# SKAARDUINO_v3_1_back.net
KiCad netlist of a schematic drawn in EAGLE
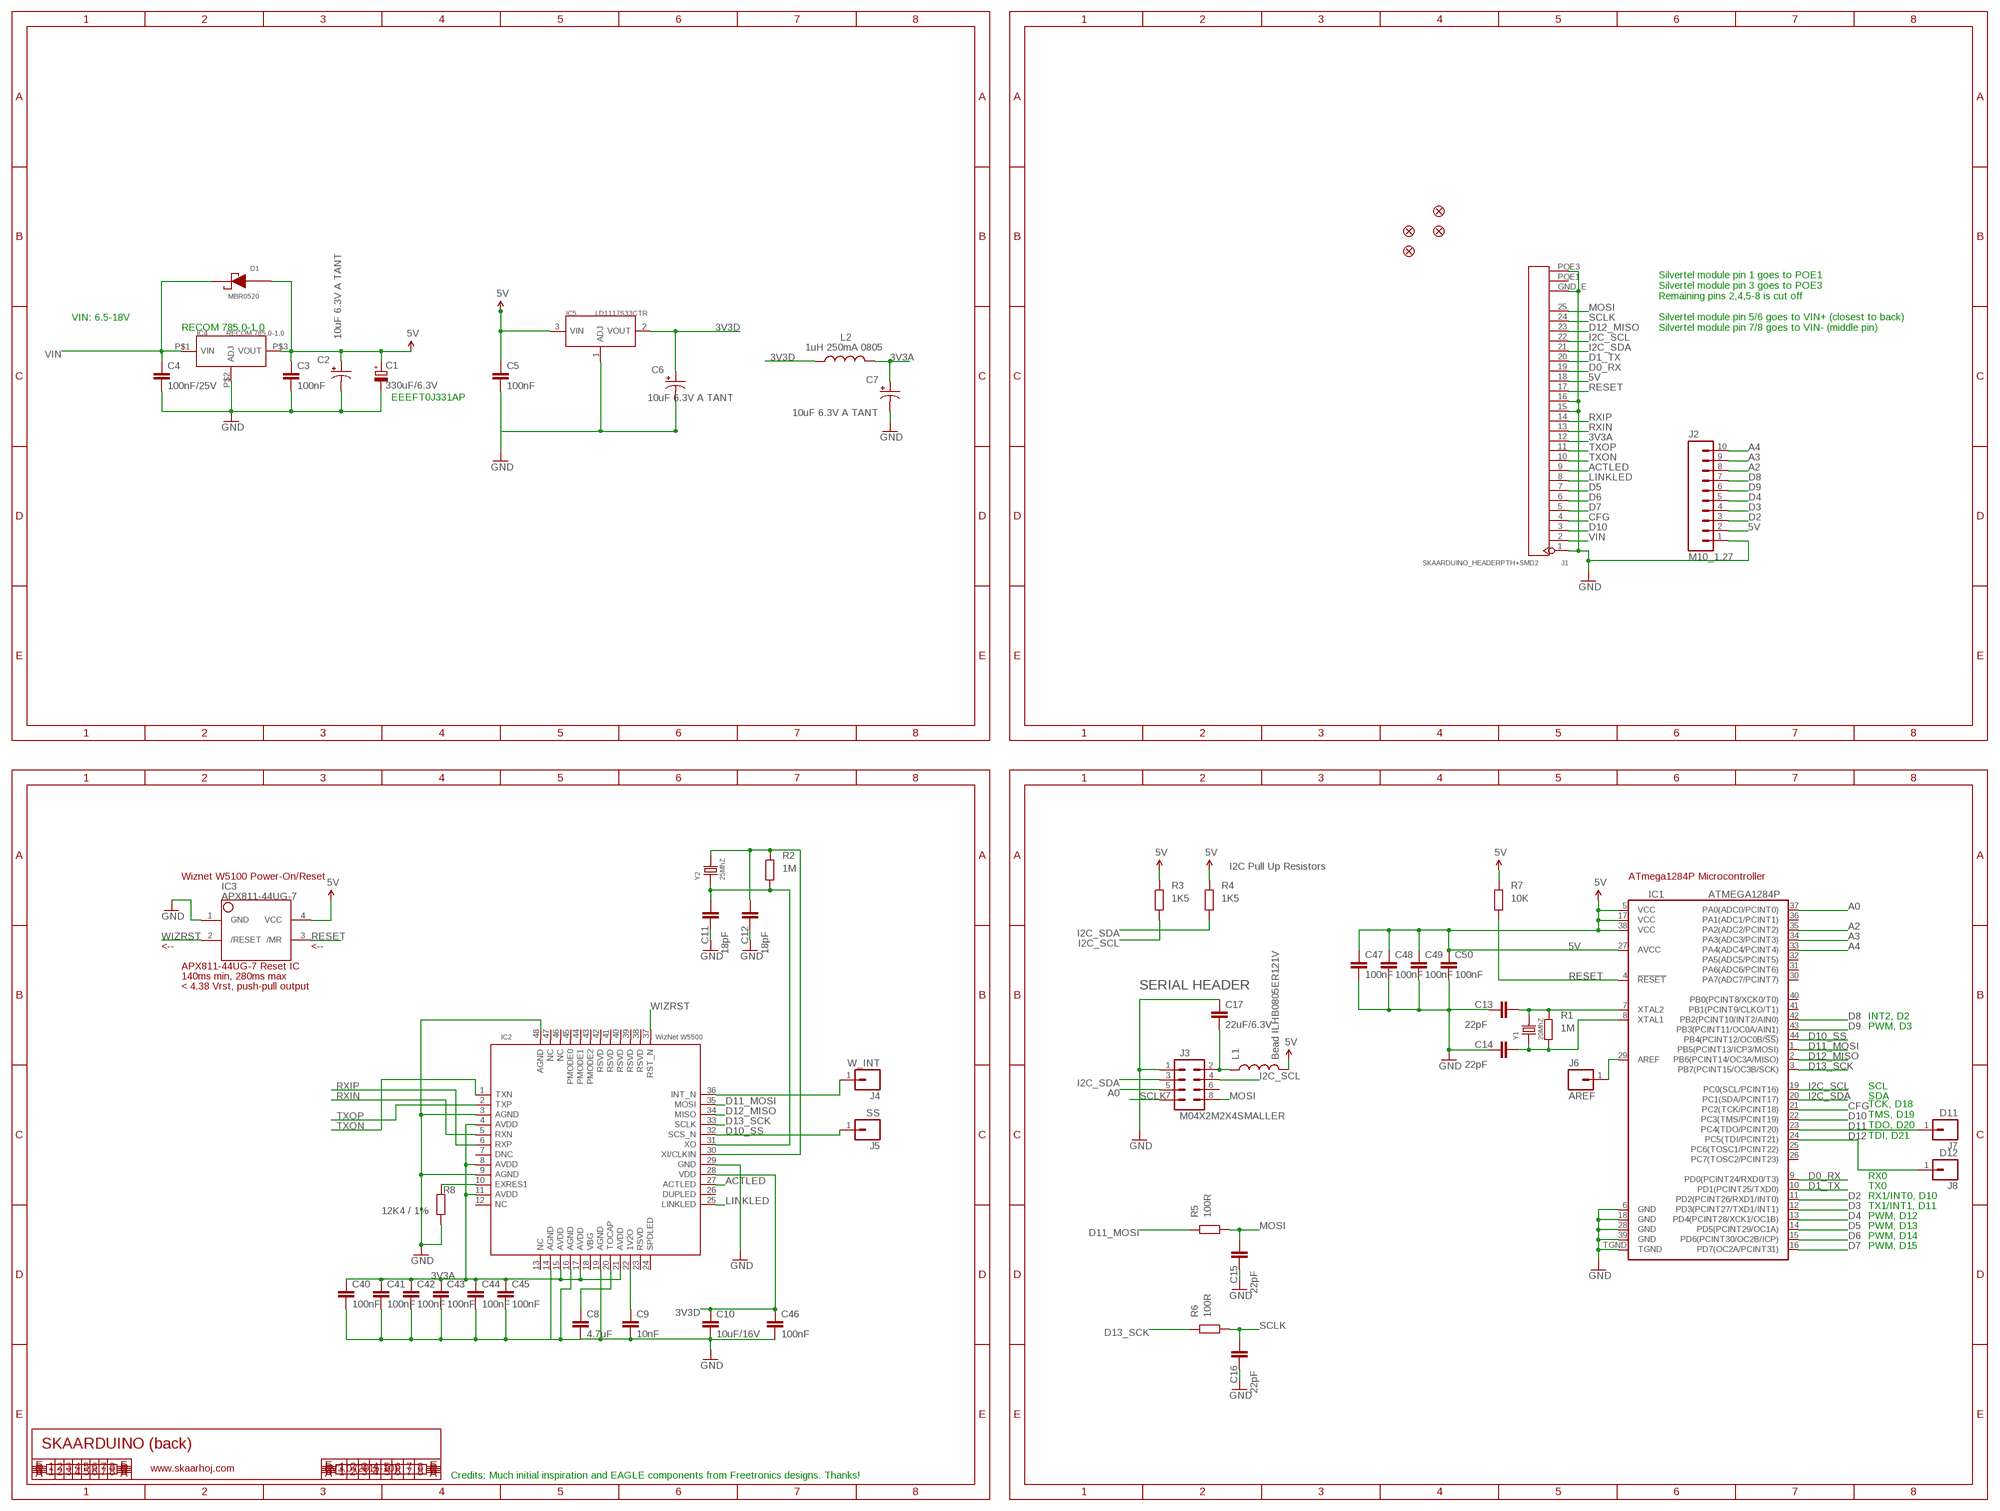
[diagram p0: schematic, sheet 1]

(export (version "E")
  (design (tool "Eeschema 10.0.6"))
  (components
    (comp (ref "C1")
      (value "330uF/6.3V")
      (footprint "eagle-import:PANASONIC_D")
      (libsource (lib "eagle-import") (part "CPOL-EUD"))
    )
    (comp (ref "C2")
      (value "10uF 6.3V A TANT")
      (footprint "eagle-import:EIA3216")
      (libsource (lib "eagle-import") (part "CAP_POL1206"))
    )
    (comp (ref "C3")
      (value "100nF")
      (footprint "eagle-import:0402C")
      (libsource (lib "eagle-import") (part "C-EU0402C"))
    )
    (comp (ref "C4")
      (value "100nF/25V")
      (footprint "eagle-import:0402C")
      (libsource (lib "eagle-import") (part "C-EU0402C"))
    )
    (comp (ref "C5")
      (value "100nF")
      (footprint "eagle-import:0402C")
      (libsource (lib "eagle-import") (part "C-EU0402C"))
    )
    (comp (ref "C6")
      (value "10uF 6.3V A TANT")
      (footprint "eagle-import:EIA3216")
      (libsource (lib "eagle-import") (part "CAP_POL1206"))
    )
    (comp (ref "C7")
      (value "10uF 6.3V A TANT")
      (footprint "eagle-import:EIA3216")
      (libsource (lib "eagle-import") (part "CAP_POL1206"))
    )
    (comp (ref "C8")
      (value "4.7uF")
      (footprint "eagle-import:0805")
      (libsource (lib "eagle-import") (part "CAP0805"))
    )
    (comp (ref "C9")
      (value "10nF")
      (footprint "eagle-import:0402C")
      (libsource (lib "eagle-import") (part "C-EU0402C"))
    )
    (comp (ref "C10")
      (value "10uF/16V")
      (footprint "eagle-import:0805")
      (libsource (lib "eagle-import") (part "CAP0805"))
    )
    (comp (ref "C11")
      (value "18pF")
      (footprint "eagle-import:0402C")
      (libsource (lib "eagle-import") (part "C-EU0402C"))
    )
    (comp (ref "C12")
      (value "18pF")
      (footprint "eagle-import:0402C")
      (libsource (lib "eagle-import") (part "C-EU0402C"))
    )
    (comp (ref "C13")
      (value "22pF")
      (footprint "eagle-import:0402C")
      (libsource (lib "eagle-import") (part "C-EU0402C"))
    )
    (comp (ref "C14")
      (value "22pF")
      (footprint "eagle-import:0402C")
      (libsource (lib "eagle-import") (part "C-EU0402C"))
    )
    (comp (ref "C15")
      (value "22pF")
      (footprint "eagle-import:0402C")
      (libsource (lib "eagle-import") (part "C-EU0402C"))
    )
    (comp (ref "C16")
      (value "22pF")
      (footprint "eagle-import:0402C")
      (libsource (lib "eagle-import") (part "C-EU0402C"))
    )
    (comp (ref "C17")
      (value "22uF/6.3V")
      (footprint "eagle-import:0805")
      (libsource (lib "eagle-import") (part "CAP0805"))
    )
    (comp (ref "C40")
      (value "100nF")
      (footprint "eagle-import:0402C")
      (libsource (lib "eagle-import") (part "C-EU0402C"))
    )
    (comp (ref "C41")
      (value "100nF")
      (footprint "eagle-import:0402C")
      (libsource (lib "eagle-import") (part "C-EU0402C"))
    )
    (comp (ref "C42")
      (value "100nF")
      (footprint "eagle-import:0402C")
      (libsource (lib "eagle-import") (part "C-EU0402C"))
    )
    (comp (ref "C43")
      (value "100nF")
      (footprint "eagle-import:0402C")
      (libsource (lib "eagle-import") (part "C-EU0402C"))
    )
    (comp (ref "C44")
      (value "100nF")
      (footprint "eagle-import:0402C")
      (libsource (lib "eagle-import") (part "C-EU0402C"))
    )
    (comp (ref "C45")
      (value "100nF")
      (footprint "eagle-import:0402C")
      (libsource (lib "eagle-import") (part "C-EU0402C"))
    )
    (comp (ref "C46")
      (value "100nF")
      (footprint "eagle-import:0402C")
      (libsource (lib "eagle-import") (part "C-EU0402C"))
    )
    (comp (ref "C47")
      (value "100nF")
      (footprint "eagle-import:0402C")
      (libsource (lib "eagle-import") (part "C-EU0402C"))
    )
    (comp (ref "C48")
      (value "100nF")
      (footprint "eagle-import:0402C")
      (libsource (lib "eagle-import") (part "C-EU0402C"))
    )
    (comp (ref "C49")
      (value "100nF")
      (footprint "eagle-import:0402C")
      (libsource (lib "eagle-import") (part "C-EU0402C"))
    )
    (comp (ref "C50")
      (value "100nF")
      (footprint "eagle-import:0402C")
      (libsource (lib "eagle-import") (part "C-EU0402C"))
    )
    (comp (ref "D1")
      (value "MBR0520")
      (footprint "eagle-import:SOD-123")
      (libsource (lib "eagle-import") (part "MBR0520"))
    )
    (comp (ref "FID1")
      (value "FIDUCIAL1X2.5")
      (footprint "eagle-import:FIDUCIAL-1X2.5")
      (libsource (lib "eagle-import") (part "FIDUCIAL1X2.5"))
    )
    (comp (ref "FID2")
      (value "FIDUCIAL1X2.5")
      (footprint "eagle-import:FIDUCIAL-1X2.5")
      (libsource (lib "eagle-import") (part "FIDUCIAL1X2.5"))
    )
    (comp (ref "FID3")
      (value "FIDUCIAL1X2.5")
      (footprint "eagle-import:FIDUCIAL-1X2.5")
      (libsource (lib "eagle-import") (part "FIDUCIAL1X2.5"))
    )
    (comp (ref "FID4")
      (value "FIDUCIAL1X2.5")
      (footprint "eagle-import:FIDUCIAL-1X2.5")
      (libsource (lib "eagle-import") (part "FIDUCIAL1X2.5"))
    )
    (comp (ref "IC1")
      (value "ATMEGA1284P")
      (footprint "eagle-import:QFN-44M1")
      (libsource (lib "eagle-import") (part "ATMEGA1284P"))
    )
    (comp (ref "IC2")
      (value "WizNet W5500")
      (footprint "eagle-import:LQFP-48")
      (libsource (lib "eagle-import") (part "DRIVER-W5500"))
    )
    (comp (ref "IC3")
      (value "APX811-44UG-7")
      (footprint "eagle-import:SOT143-R")
      (libsource (lib "eagle-import") (part "APX81X-RESET-IC"))
    )
    (comp (ref "IC4")
      (value "RECOM 785.0-1.0")
      (footprint "eagle-import:RECOM_785.0-1.0")
      (libsource (lib "eagle-import") (part "PMIC-LM317EMP"))
    )
    (comp (ref "IC5")
      (value "LD1117S33CTR")
      (footprint "eagle-import:SOT-223-UPRIGHT")
      (libsource (lib "eagle-import") (part "PMIC-LM317EMPUPRIGHT"))
    )
    (comp (ref "J1")
      (value "SKAARDUINO_HEADERPTH+SMD2")
      (footprint "eagle-import:SKAARDUINO_PTH_SMD2_HEADER")
      (libsource (lib "eagle-import") (part "SKAARDUINO_HEADERPTH+SMD2"))
    )
    (comp (ref "J2")
      (value "M10_1.27")
      (footprint "eagle-import:M10X1")
      (libsource (lib "eagle-import") (part "M10_1.27"))
    )
    (comp (ref "J3")
      (value "M04X2M2X4SMALLER")
      (footprint "eagle-import:M2X4SMALLER")
      (libsource (lib "eagle-import") (part "M04X2M2X4SMALLER"))
    )
    (comp (ref "J4")
      (value "W_INT")
      (footprint "eagle-import:M1X1")
      (libsource (lib "eagle-import") (part "M1X1TEST"))
    )
    (comp (ref "J5")
      (value "SS")
      (footprint "eagle-import:M1X1")
      (libsource (lib "eagle-import") (part "M1X1TEST"))
    )
    (comp (ref "J6")
      (value "AREF")
      (footprint "eagle-import:M1X1")
      (libsource (lib "eagle-import") (part "M1X1TEST"))
    )
    (comp (ref "J7")
      (value "D11")
      (footprint "eagle-import:M1X1")
      (libsource (lib "eagle-import") (part "M1X1TEST"))
    )
    (comp (ref "J8")
      (value "D12")
      (footprint "eagle-import:M1X1")
      (libsource (lib "eagle-import") (part "M1X1TEST"))
    )
    (comp (ref "L1")
      (value "Bead ILHB0805ER121V")
      (footprint "eagle-import:0805")
      (libsource (lib "eagle-import") (part "INDUCTOR0805"))
    )
    (comp (ref "L2")
      (value "1uH 250mA 0805")
      (footprint "eagle-import:L2012C")
      (libsource (lib "eagle-import") (part "L-USL2012C"))
    )
    (comp (ref "R1")
      (value "1M")
      (footprint "eagle-import:0402")
      (libsource (lib "eagle-import") (part "RESISTOR0402"))
    )
    (comp (ref "R2")
      (value "1M")
      (footprint "eagle-import:0402")
      (libsource (lib "eagle-import") (part "RESISTOR0402"))
    )
    (comp (ref "R3")
      (value "1K5")
      (footprint "eagle-import:0402")
      (libsource (lib "eagle-import") (part "RESISTOR0402"))
    )
    (comp (ref "R4")
      (value "1K5")
      (footprint "eagle-import:0402")
      (libsource (lib "eagle-import") (part "RESISTOR0402"))
    )
    (comp (ref "R5")
      (value "100R")
      (footprint "eagle-import:0402")
      (libsource (lib "eagle-import") (part "RESISTOR0402"))
    )
    (comp (ref "R6")
      (value "100R")
      (footprint "eagle-import:0402")
      (libsource (lib "eagle-import") (part "RESISTOR0402"))
    )
    (comp (ref "R7")
      (value "10K")
      (footprint "eagle-import:0402")
      (libsource (lib "eagle-import") (part "RESISTOR0402"))
    )
    (comp (ref "R8")
      (value "12K4 / 1%")
      (footprint "eagle-import:0402")
      (libsource (lib "eagle-import") (part "RESISTOR0402"))
    )
    (comp (ref "Y1")
      (value "20MhZ")
      (footprint "eagle-import:X2-SMD-5.0X3.2X1.3MM")
      (fields (field (name "MPN") "X053201602002"))
      (libsource (lib "eagle-import") (part "SMD-CRYSTAL-16MHZ-8PF-20PPM-40R(2P-5.0X3.2MM)"))
    )
    (comp (ref "Y2")
      (value "25MhZ")
      (footprint "eagle-import:X2-SMD-5.0X3.2X1.3MM")
      (fields (field (name "MPN") "X053201602002"))
      (libsource (lib "eagle-import") (part "SMD-CRYSTAL-16MHZ-8PF-20PPM-40R(2P-5.0X3.2MM)"))
    )
  )
  (nets
    (net (code "1") (name "3V3A") (class "Default")
      (node (ref "C40") (pin "1") (pinfunction "1_1") (pintype "passive"))
      (node (ref "C41") (pin "1") (pinfunction "1_1") (pintype "passive"))
      (node (ref "C42") (pin "1") (pinfunction "1_1") (pintype "passive"))
      (node (ref "C43") (pin "1") (pinfunction "1_1") (pintype "passive"))
      (node (ref "C44") (pin "1") (pinfunction "1_1") (pintype "passive"))
      (node (ref "C45") (pin "1") (pinfunction "1_1") (pintype "passive"))
      (node (ref "C7") (pin "A") (pinfunction "+_A") (pintype "passive"))
      (node (ref "IC2") (pin "11") (pinfunction "AVDD_11") (pintype "passive"))
      (node (ref "IC2") (pin "15") (pinfunction "AVDD_15") (pintype "passive"))
      (node (ref "IC2") (pin "17") (pinfunction "AVDD_17") (pintype "passive"))
      (node (ref "IC2") (pin "21") (pinfunction "AVDD_21") (pintype "passive"))
      (node (ref "IC2") (pin "4") (pinfunction "AVDD_4") (pintype "passive"))
      (node (ref "IC2") (pin "8") (pinfunction "AVDD_8") (pintype "passive"))
      (node (ref "J1") (pin "12") (pinfunction "12_12") (pintype "bidirectional"))
      (node (ref "L2") (pin "2") (pinfunction "2_2") (pintype "passive"))
    )
    (net (code "2") (name "3V3D") (class "Default")
      (node (ref "C10") (pin "1") (pinfunction "1_1") (pintype "passive"))
      (node (ref "C46") (pin "1") (pinfunction "1_1") (pintype "passive"))
      (node (ref "C6") (pin "A") (pinfunction "+_A") (pintype "passive"))
      (node (ref "IC2") (pin "28") (pinfunction "VDD_28") (pintype "passive"))
      (node (ref "IC5") (pin "2") (pinfunction "VOUT_2") (pintype "bidirectional"))
      (node (ref "L2") (pin "1") (pinfunction "1_1") (pintype "passive"))
    )
    (net (code "3") (name "5V") (class "Default")
      (node (ref "C1") (pin "+") (pinfunction "+_+") (pintype "passive"))
      (node (ref "C2") (pin "A") (pinfunction "+_A") (pintype "passive"))
      (node (ref "C3") (pin "1") (pinfunction "1_1") (pintype "passive"))
      (node (ref "C47") (pin "1") (pinfunction "1_1") (pintype "passive"))
      (node (ref "C48") (pin "1") (pinfunction "1_1") (pintype "passive"))
      (node (ref "C49") (pin "1") (pinfunction "1_1") (pintype "passive"))
      (node (ref "C5") (pin "1") (pinfunction "1_1") (pintype "passive"))
      (node (ref "C50") (pin "1") (pinfunction "1_1") (pintype "passive"))
      (node (ref "D1") (pin "2") (pinfunction "AN_2") (pintype "passive"))
      (node (ref "IC1") (pin "17") (pinfunction "VCC_17") (pintype "bidirectional"))
      (node (ref "IC1") (pin "27") (pinfunction "AVCC_27") (pintype "bidirectional"))
      (node (ref "IC1") (pin "38") (pinfunction "VCC_38") (pintype "bidirectional"))
      (node (ref "IC1") (pin "5") (pinfunction "VCC_5") (pintype "bidirectional"))
      (node (ref "IC3") (pin "4") (pinfunction "VCC_4") (pintype "power_in"))
      (node (ref "IC4") (pin "P$3") (pinfunction "VOUT_P$3") (pintype "bidirectional"))
      (node (ref "IC5") (pin "3") (pinfunction "VIN_3") (pintype "bidirectional"))
      (node (ref "J1") (pin "18") (pinfunction "18_18") (pintype "bidirectional"))
      (node (ref "J2") (pin "2") (pinfunction "2_2") (pintype "passive"))
      (node (ref "L1") (pin "2") (pinfunction "2_2") (pintype "passive"))
      (node (ref "R3") (pin "2") (pinfunction "2_2") (pintype "passive"))
      (node (ref "R4") (pin "2") (pinfunction "2_2") (pintype "passive"))
      (node (ref "R7") (pin "2") (pinfunction "2_2") (pintype "passive"))
    )
    (net (code "4") (name "A0") (class "Default")
      (node (ref "IC1") (pin "37") (pinfunction "PA0(ADC0/PCINT0)_37") (pintype "bidirectional"))
      (node (ref "J3") (pin "5") (pinfunction "5_5") (pintype "passive"))
    )
    (net (code "5") (name "A2") (class "Default")
      (node (ref "IC1") (pin "35") (pinfunction "PA2(ADC2/PCINT2)_35") (pintype "bidirectional"))
      (node (ref "J2") (pin "8") (pinfunction "8_8") (pintype "passive"))
    )
    (net (code "6") (name "A3") (class "Default")
      (node (ref "IC1") (pin "34") (pinfunction "PA3(ADC3/PCINT3)_34") (pintype "bidirectional"))
      (node (ref "J2") (pin "9") (pinfunction "9_9") (pintype "passive"))
    )
    (net (code "7") (name "A4") (class "Default")
      (node (ref "IC1") (pin "33") (pinfunction "PA4(ADC4/PCINT4)_33") (pintype "bidirectional"))
      (node (ref "J2") (pin "10") (pinfunction "10_10") (pintype "passive"))
    )
    (net (code "8") (name "ACTLED") (class "Default")
      (node (ref "IC2") (pin "27") (pinfunction "ACTLED_27") (pintype "passive"))
      (node (ref "J1") (pin "9") (pinfunction "9_9") (pintype "bidirectional"))
    )
    (net (code "9") (name "CFG") (class "Default")
      (node (ref "IC1") (pin "21") (pinfunction "PC2(TCK/PCINT18)_21") (pintype "bidirectional"))
      (node (ref "J1") (pin "4") (pinfunction "4_4") (pintype "bidirectional"))
    )
    (net (code "10") (name "D0_RX") (class "Default")
      (node (ref "IC1") (pin "9") (pinfunction "PD0(PCINT24/RXD0/T3)_9") (pintype "bidirectional"))
      (node (ref "J1") (pin "19") (pinfunction "19_19") (pintype "bidirectional"))
    )
    (net (code "11") (name "D1_TX") (class "Default")
      (node (ref "IC1") (pin "10") (pinfunction "PD1(PCINT25/TXD0)_10") (pintype "bidirectional"))
      (node (ref "J1") (pin "20") (pinfunction "20_20") (pintype "bidirectional"))
    )
    (net (code "12") (name "D2") (class "Default")
      (node (ref "IC1") (pin "11") (pinfunction "PD2(PCINT26/RXD1/INT0)_11") (pintype "bidirectional"))
      (node (ref "J2") (pin "3") (pinfunction "3_3") (pintype "passive"))
    )
    (net (code "13") (name "D3") (class "Default")
      (node (ref "IC1") (pin "12") (pinfunction "PD3(PCINT27/TXD1/INT1)_12") (pintype "bidirectional"))
      (node (ref "J2") (pin "4") (pinfunction "4_4") (pintype "passive"))
    )
    (net (code "14") (name "D4") (class "Default")
      (node (ref "IC1") (pin "13") (pinfunction "PD4(PCINT28/XCK1/OC1B)_13") (pintype "bidirectional"))
      (node (ref "J2") (pin "5") (pinfunction "5_5") (pintype "passive"))
    )
    (net (code "15") (name "D5") (class "Default")
      (node (ref "IC1") (pin "14") (pinfunction "PD5(PCINT29/OC1A)_14") (pintype "bidirectional"))
      (node (ref "J1") (pin "7") (pinfunction "7_7") (pintype "bidirectional"))
    )
    (net (code "16") (name "D6") (class "Default")
      (node (ref "IC1") (pin "15") (pinfunction "PD6(PCINT30/OC2B/ICP)_15") (pintype "bidirectional"))
      (node (ref "J1") (pin "6") (pinfunction "6_6") (pintype "bidirectional"))
    )
    (net (code "17") (name "D7") (class "Default")
      (node (ref "IC1") (pin "16") (pinfunction "PD7(OC2A/PCINT31)_16") (pintype "bidirectional"))
      (node (ref "J1") (pin "5") (pinfunction "5_5") (pintype "bidirectional"))
    )
    (net (code "18") (name "D8") (class "Default")
      (node (ref "IC1") (pin "42") (pinfunction "PB2(PCINT10/INT2/AIN0)_42") (pintype "bidirectional"))
      (node (ref "J2") (pin "7") (pinfunction "7_7") (pintype "passive"))
    )
    (net (code "19") (name "D9") (class "Default")
      (node (ref "IC1") (pin "43") (pinfunction "PB3(PCINT11/OC0A/AIN1)_43") (pintype "bidirectional"))
      (node (ref "J2") (pin "6") (pinfunction "6_6") (pintype "passive"))
    )
    (net (code "20") (name "D10") (class "Default")
      (node (ref "IC1") (pin "22") (pinfunction "PC3(TMS/PCINT19)_22") (pintype "bidirectional"))
      (node (ref "J1") (pin "3") (pinfunction "3_3") (pintype "bidirectional"))
    )
    (net (code "21") (name "D10_SS") (class "Default")
      (node (ref "IC1") (pin "44") (pinfunction "PB4(PCINT12/OC0B/~{SS})_44") (pintype "bidirectional"))
      (node (ref "IC2") (pin "32") (pinfunction "SCS_N_32") (pintype "passive"))
      (node (ref "J5") (pin "1") (pinfunction "5_1") (pintype "passive"))
    )
    (net (code "22") (name "D11") (class "Default")
      (node (ref "IC1") (pin "23") (pinfunction "PC4(TDO/PCINT20)_23") (pintype "bidirectional"))
      (node (ref "J7") (pin "1") (pinfunction "5_1") (pintype "passive"))
    )
    (net (code "23") (name "D11_MOSI") (class "Default")
      (node (ref "IC1") (pin "1") (pinfunction "PB5(PCINT13/ICP3/MOSI)_1") (pintype "bidirectional"))
      (node (ref "IC2") (pin "35") (pinfunction "MOSI_35") (pintype "passive"))
      (node (ref "R5") (pin "2") (pinfunction "2_2") (pintype "passive"))
    )
    (net (code "24") (name "D12") (class "Default")
      (node (ref "IC1") (pin "24") (pinfunction "PC5(TDI/PCINT21)_24") (pintype "bidirectional"))
      (node (ref "J8") (pin "1") (pinfunction "5_1") (pintype "passive"))
    )
    (net (code "25") (name "D12_MISO") (class "Default")
      (node (ref "IC1") (pin "2") (pinfunction "PB6(PCINT14/OC3A/MISO)_2") (pintype "bidirectional"))
      (node (ref "IC2") (pin "34") (pinfunction "MISO_34") (pintype "passive"))
      (node (ref "J1") (pin "23") (pinfunction "23_23") (pintype "bidirectional"))
    )
    (net (code "26") (name "D13_SCK") (class "Default")
      (node (ref "IC1") (pin "3") (pinfunction "PB7(PCINT15/OC3B/SCK)_3") (pintype "bidirectional"))
      (node (ref "IC2") (pin "33") (pinfunction "SCLK_33") (pintype "passive"))
      (node (ref "R6") (pin "2") (pinfunction "2_2") (pintype "passive"))
    )
    (net (code "27") (name "GND") (class "Default")
      (node (ref "C1") (pin "-") (pinfunction "-_-") (pintype "passive"))
      (node (ref "C10") (pin "2") (pinfunction "2_2") (pintype "passive"))
      (node (ref "C11") (pin "1") (pinfunction "1_1") (pintype "passive"))
      (node (ref "C12") (pin "1") (pinfunction "1_1") (pintype "passive"))
      (node (ref "C13") (pin "1") (pinfunction "1_1") (pintype "passive"))
      (node (ref "C14") (pin "1") (pinfunction "1_1") (pintype "passive"))
      (node (ref "C15") (pin "1") (pinfunction "1_1") (pintype "passive"))
      (node (ref "C16") (pin "1") (pinfunction "1_1") (pintype "passive"))
      (node (ref "C17") (pin "1") (pinfunction "1_1") (pintype "passive"))
      (node (ref "C2") (pin "C") (pinfunction "-_C") (pintype "passive"))
      (node (ref "C3") (pin "2") (pinfunction "2_2") (pintype "passive"))
      (node (ref "C4") (pin "2") (pinfunction "2_2") (pintype "passive"))
      (node (ref "C40") (pin "2") (pinfunction "2_2") (pintype "passive"))
      (node (ref "C41") (pin "2") (pinfunction "2_2") (pintype "passive"))
      (node (ref "C42") (pin "2") (pinfunction "2_2") (pintype "passive"))
      (node (ref "C43") (pin "2") (pinfunction "2_2") (pintype "passive"))
      (node (ref "C44") (pin "2") (pinfunction "2_2") (pintype "passive"))
      (node (ref "C45") (pin "2") (pinfunction "2_2") (pintype "passive"))
      (node (ref "C46") (pin "2") (pinfunction "2_2") (pintype "passive"))
      (node (ref "C47") (pin "2") (pinfunction "2_2") (pintype "passive"))
      (node (ref "C48") (pin "2") (pinfunction "2_2") (pintype "passive"))
      (node (ref "C49") (pin "2") (pinfunction "2_2") (pintype "passive"))
      (node (ref "C5") (pin "2") (pinfunction "2_2") (pintype "passive"))
      (node (ref "C50") (pin "2") (pinfunction "2_2") (pintype "passive"))
      (node (ref "C6") (pin "C") (pinfunction "-_C") (pintype "passive"))
      (node (ref "C7") (pin "C") (pinfunction "-_C") (pintype "passive"))
      (node (ref "C8") (pin "2") (pinfunction "2_2") (pintype "passive"))
      (node (ref "C9") (pin "2") (pinfunction "2_2") (pintype "passive"))
      (node (ref "IC1") (pin "18") (pinfunction "GND_18") (pintype "bidirectional"))
      (node (ref "IC1") (pin "28") (pinfunction "GND_28") (pintype "bidirectional"))
      (node (ref "IC1") (pin "39") (pinfunction "GND_39") (pintype "bidirectional"))
      (node (ref "IC1") (pin "6") (pinfunction "GND_6") (pintype "bidirectional"))
      (node (ref "IC1") (pin "TGND") (pinfunction "TGND_TGND") (pintype "bidirectional"))
      (node (ref "IC2") (pin "14") (pinfunction "AGND_14") (pintype "passive"))
      (node (ref "IC2") (pin "16") (pinfunction "AGND_16") (pintype "passive"))
      (node (ref "IC2") (pin "19") (pinfunction "AGND_19") (pintype "passive"))
      (node (ref "IC2") (pin "29") (pinfunction "GND_29") (pintype "passive"))
      (node (ref "IC2") (pin "3") (pinfunction "AGND_3") (pintype "passive"))
      (node (ref "IC2") (pin "48") (pinfunction "AGND_48") (pintype "passive"))
      (node (ref "IC2") (pin "9") (pinfunction "AGND_9") (pintype "passive"))
      (node (ref "IC3") (pin "1") (pinfunction "GND_1") (pintype "power_in"))
      (node (ref "IC4") (pin "P$2") (pinfunction "ADJ_P$2") (pintype "bidirectional"))
      (node (ref "IC5") (pin "1") (pinfunction "ADJ_1") (pintype "bidirectional"))
      (node (ref "J1") (pin "1") (pinfunction "1_1") (pintype "bidirectional"))
      (node (ref "J1") (pin "15") (pinfunction "15_15") (pintype "bidirectional"))
      (node (ref "J1") (pin "16") (pinfunction "16_16") (pintype "bidirectional"))
      (node (ref "J1") (pin "GND_E") (pinfunction "26_GND_E") (pintype "bidirectional"))
      (node (ref "J1") (pin "POE3") (pinfunction "28_POE3") (pintype "bidirectional"))
      (node (ref "J2") (pin "1") (pinfunction "1_1") (pintype "passive"))
      (node (ref "J3") (pin "1") (pinfunction "1_1") (pintype "passive"))
      (node (ref "R8") (pin "1") (pinfunction "1_1") (pintype "passive"))
    )
    (net (code "28") (name "I2C_SCL") (class "Default")
      (node (ref "IC1") (pin "19") (pinfunction "PC0(SCL/PCINT16)_19") (pintype "bidirectional"))
      (node (ref "J1") (pin "22") (pinfunction "22_22") (pintype "bidirectional"))
      (node (ref "J3") (pin "4") (pinfunction "4_4") (pintype "passive"))
      (node (ref "R3") (pin "1") (pinfunction "1_1") (pintype "passive"))
    )
    (net (code "29") (name "I2C_SDA") (class "Default")
      (node (ref "IC1") (pin "20") (pinfunction "PC1(SDA/PCINT17)_20") (pintype "bidirectional"))
      (node (ref "J1") (pin "21") (pinfunction "21_21") (pintype "bidirectional"))
      (node (ref "J3") (pin "3") (pinfunction "3_3") (pintype "passive"))
      (node (ref "R4") (pin "1") (pinfunction "1_1") (pintype "passive"))
    )
    (net (code "30") (name "LINKLED") (class "Default")
      (node (ref "IC2") (pin "25") (pinfunction "LINKLED_25") (pintype "passive"))
      (node (ref "J1") (pin "8") (pinfunction "8_8") (pintype "bidirectional"))
    )
    (net (code "31") (name "MOSI") (class "Default")
      (node (ref "C15") (pin "2") (pinfunction "2_2") (pintype "passive"))
      (node (ref "J1") (pin "25") (pinfunction "25_25") (pintype "bidirectional"))
      (node (ref "J3") (pin "8") (pinfunction "8_8") (pintype "passive"))
      (node (ref "R5") (pin "1") (pinfunction "1_1") (pintype "passive"))
    )
    (net (code "32") (name "Net-(C17-Pad2)") (class "Default")
      (node (ref "C17") (pin "2") (pinfunction "2_2") (pintype "passive"))
      (node (ref "J3") (pin "2") (pinfunction "2_2") (pintype "passive"))
      (node (ref "L1") (pin "1") (pinfunction "1_1") (pintype "passive"))
    )
    (net (code "33") (name "Net-(IC1-AREF)") (class "Default")
      (node (ref "IC1") (pin "29") (pinfunction "AREF_29") (pintype "bidirectional"))
      (node (ref "J6") (pin "1") (pinfunction "5_1") (pintype "passive"))
    )
    (net (code "34") (name "Net-(IC1-XTAL1)") (class "Default")
      (node (ref "C14") (pin "2") (pinfunction "2_2") (pintype "passive"))
      (node (ref "IC1") (pin "8") (pinfunction "XTAL1_8") (pintype "bidirectional"))
      (node (ref "R1") (pin "1") (pinfunction "1_1") (pintype "passive"))
      (node (ref "Y1") (pin "1") (pinfunction "1_1") (pintype "passive"))
    )
    (net (code "35") (name "Net-(IC1-XTAL2)") (class "Default")
      (node (ref "C13") (pin "2") (pinfunction "2_2") (pintype "passive"))
      (node (ref "IC1") (pin "7") (pinfunction "XTAL2_7") (pintype "bidirectional"))
      (node (ref "R1") (pin "2") (pinfunction "2_2") (pintype "passive"))
      (node (ref "Y1") (pin "2") (pinfunction "2_2") (pintype "passive"))
    )
    (net (code "36") (name "Net-(IC2-1V2O)") (class "Default")
      (node (ref "C9") (pin "1") (pinfunction "1_1") (pintype "passive"))
      (node (ref "IC2") (pin "22") (pinfunction "1V2O_22") (pintype "passive"))
    )
    (net (code "37") (name "Net-(IC2-EXRES1)") (class "Default")
      (node (ref "IC2") (pin "10") (pinfunction "EXRES1_10") (pintype "passive"))
      (node (ref "R8") (pin "2") (pinfunction "2_2") (pintype "passive"))
    )
    (net (code "38") (name "Net-(IC2-INT_N)") (class "Default")
      (node (ref "IC2") (pin "36") (pinfunction "INT_N_36") (pintype "passive"))
      (node (ref "J4") (pin "1") (pinfunction "5_1") (pintype "passive"))
    )
    (net (code "39") (name "Net-(IC2-TOCAP)") (class "Default")
      (node (ref "C8") (pin "1") (pinfunction "1_1") (pintype "passive"))
      (node (ref "IC2") (pin "20") (pinfunction "TOCAP_20") (pintype "passive"))
    )
    (net (code "40") (name "Net-(IC2-XI{slash}CLKIN)") (class "Default")
      (node (ref "C12") (pin "2") (pinfunction "2_2") (pintype "passive"))
      (node (ref "IC2") (pin "30") (pinfunction "XI/CLKIN_30") (pintype "passive"))
      (node (ref "R2") (pin "2") (pinfunction "2_2") (pintype "passive"))
      (node (ref "Y2") (pin "2") (pinfunction "2_2") (pintype "passive"))
    )
    (net (code "41") (name "Net-(IC2-XO)") (class "Default")
      (node (ref "C11") (pin "2") (pinfunction "2_2") (pintype "passive"))
      (node (ref "IC2") (pin "31") (pinfunction "XO_31") (pintype "passive"))
      (node (ref "R2") (pin "1") (pinfunction "1_1") (pintype "passive"))
      (node (ref "Y2") (pin "1") (pinfunction "1_1") (pintype "passive"))
    )
    (net (code "42") (name "RESET") (class "Default")
      (node (ref "IC1") (pin "4") (pinfunction "~{RESET}_4") (pintype "bidirectional"))
      (node (ref "IC3") (pin "3") (pinfunction "/MR_3") (pintype "input"))
      (node (ref "J1") (pin "17") (pinfunction "17_17") (pintype "bidirectional"))
      (node (ref "R7") (pin "1") (pinfunction "1_1") (pintype "passive"))
    )
    (net (code "43") (name "RXIN") (class "Default")
      (node (ref "IC2") (pin "5") (pinfunction "RXN_5") (pintype "passive"))
      (node (ref "J1") (pin "13") (pinfunction "13_13") (pintype "bidirectional"))
    )
    (net (code "44") (name "RXIP") (class "Default")
      (node (ref "IC2") (pin "6") (pinfunction "RXP_6") (pintype "passive"))
      (node (ref "J1") (pin "14") (pinfunction "14_14") (pintype "bidirectional"))
    )
    (net (code "45") (name "SCLK") (class "Default")
      (node (ref "C16") (pin "2") (pinfunction "2_2") (pintype "passive"))
      (node (ref "J1") (pin "24") (pinfunction "24_24") (pintype "bidirectional"))
      (node (ref "J3") (pin "7") (pinfunction "7_7") (pintype "passive"))
      (node (ref "R6") (pin "1") (pinfunction "1_1") (pintype "passive"))
    )
    (net (code "46") (name "TXON") (class "Default")
      (node (ref "IC2") (pin "1") (pinfunction "TXN_1") (pintype "passive"))
      (node (ref "J1") (pin "10") (pinfunction "10_10") (pintype "bidirectional"))
    )
    (net (code "47") (name "TXOP") (class "Default")
      (node (ref "IC2") (pin "2") (pinfunction "TXP_2") (pintype "passive"))
      (node (ref "J1") (pin "11") (pinfunction "11_11") (pintype "bidirectional"))
    )
    (net (code "48") (name "VIN") (class "Default")
      (node (ref "C4") (pin "1") (pinfunction "1_1") (pintype "passive"))
      (node (ref "D1") (pin "1") (pinfunction "CA_1") (pintype "passive"))
      (node (ref "IC4") (pin "P$1") (pinfunction "VIN_P$1") (pintype "bidirectional"))
      (node (ref "J1") (pin "2") (pinfunction "2_2") (pintype "bidirectional"))
    )
    (net (code "49") (name "WIZRST") (class "Default")
      (node (ref "IC2") (pin "37") (pinfunction "RST_N_37") (pintype "passive"))
      (node (ref "IC3") (pin "2") (pinfunction "/RESET_2") (pintype "output"))
    )
    (net (code "50") (name "unconnected-(IC1-PA1(ADC1{slash}PCINT1)-Pad36)") (class "Default")
      (node (ref "IC1") (pin "36") (pinfunction "PA1(ADC1/PCINT1)_36") (pintype "bidirectional"))
    )
    (net (code "51") (name "unconnected-(IC1-PA5(ADC5{slash}PCINT5)-Pad32)") (class "Default")
      (node (ref "IC1") (pin "32") (pinfunction "PA5(ADC5/PCINT5)_32") (pintype "bidirectional"))
    )
    (net (code "52") (name "unconnected-(IC1-PA6(ADC6{slash}PCINT6)-Pad31)") (class "Default")
      (node (ref "IC1") (pin "31") (pinfunction "PA6(ADC6/PCINT6)_31") (pintype "bidirectional"))
    )
    (net (code "53") (name "unconnected-(IC1-PA7(ADC7{slash}PCINT7)-Pad30)") (class "Default")
      (node (ref "IC1") (pin "30") (pinfunction "PA7(ADC7/PCINT7)_30") (pintype "bidirectional"))
    )
    (net (code "54") (name "unconnected-(IC1-PB0(PCINT8{slash}XCK0{slash}T0)-Pad40)") (class "Default")
      (node (ref "IC1") (pin "40") (pinfunction "PB0(PCINT8/XCK0/T0)_40") (pintype "bidirectional"))
    )
    (net (code "55") (name "unconnected-(IC1-PB1(PCINT9{slash}CLKO{slash}T1)-Pad41)") (class "Default")
      (node (ref "IC1") (pin "41") (pinfunction "PB1(PCINT9/CLKO/T1)_41") (pintype "bidirectional"))
    )
    (net (code "56") (name "unconnected-(IC1-PC6(TOSC1{slash}PCINT22)-Pad25)") (class "Default")
      (node (ref "IC1") (pin "25") (pinfunction "PC6(TOSC1/PCINT22)_25") (pintype "bidirectional"))
    )
    (net (code "57") (name "unconnected-(IC1-PC7(TOSC2{slash}PCINT23)-Pad26)") (class "Default")
      (node (ref "IC1") (pin "26") (pinfunction "PC7(TOSC2/PCINT23)_26") (pintype "bidirectional"))
    )
    (net (code "58") (name "unconnected-(IC2-DNC-Pad7)") (class "Default")
      (node (ref "IC2") (pin "7") (pinfunction "DNC_7") (pintype "passive"))
    )
    (net (code "59") (name "unconnected-(IC2-DUPLED-Pad26)") (class "Default")
      (node (ref "IC2") (pin "26") (pinfunction "DUPLED_26") (pintype "passive"))
    )
    (net (code "60") (name "unconnected-(IC2-NC-Pad12)") (class "Default")
      (node (ref "IC2") (pin "12") (pinfunction "NC_12") (pintype "passive"))
    )
    (net (code "61") (name "unconnected-(IC2-NC-Pad13)") (class "Default")
      (node (ref "IC2") (pin "13") (pinfunction "NC_13") (pintype "passive"))
    )
    (net (code "62") (name "unconnected-(IC2-NC-Pad46)") (class "Default")
      (node (ref "IC2") (pin "46") (pinfunction "NC_46") (pintype "passive"))
    )
    (net (code "63") (name "unconnected-(IC2-NC-Pad47)") (class "Default")
      (node (ref "IC2") (pin "47") (pinfunction "NC_47") (pintype "passive"))
    )
    (net (code "64") (name "unconnected-(IC2-PMODE0-Pad45)") (class "Default")
      (node (ref "IC2") (pin "45") (pinfunction "PMODE0_45") (pintype "passive"))
    )
    (net (code "65") (name "unconnected-(IC2-PMODE1-Pad44)") (class "Default")
      (node (ref "IC2") (pin "44") (pinfunction "PMODE1_44") (pintype "passive"))
    )
    (net (code "66") (name "unconnected-(IC2-PMODE2-Pad43)") (class "Default")
      (node (ref "IC2") (pin "43") (pinfunction "PMODE2_43") (pintype "passive"))
    )
    (net (code "67") (name "unconnected-(IC2-RSVD-Pad23)") (class "Default")
      (node (ref "IC2") (pin "23") (pinfunction "RSVD_23") (pintype "passive"))
    )
    (net (code "68") (name "unconnected-(IC2-RSVD-Pad38)") (class "Default")
      (node (ref "IC2") (pin "38") (pinfunction "RSVD_38") (pintype "passive"))
    )
    (net (code "69") (name "unconnected-(IC2-RSVD-Pad39)") (class "Default")
      (node (ref "IC2") (pin "39") (pinfunction "RSVD_39") (pintype "passive"))
    )
    (net (code "70") (name "unconnected-(IC2-RSVD-Pad40)") (class "Default")
      (node (ref "IC2") (pin "40") (pinfunction "RSVD_40") (pintype "passive"))
    )
    (net (code "71") (name "unconnected-(IC2-RSVD-Pad41)") (class "Default")
      (node (ref "IC2") (pin "41") (pinfunction "RSVD_41") (pintype "passive"))
    )
    (net (code "72") (name "unconnected-(IC2-RSVD-Pad42)") (class "Default")
      (node (ref "IC2") (pin "42") (pinfunction "RSVD_42") (pintype "passive"))
    )
    (net (code "73") (name "unconnected-(IC2-SPDLED-Pad24)") (class "Default")
      (node (ref "IC2") (pin "24") (pinfunction "SPDLED_24") (pintype "passive"))
    )
    (net (code "74") (name "unconnected-(IC2-VBG-Pad18)") (class "Default")
      (node (ref "IC2") (pin "18") (pinfunction "VBG_18") (pintype "passive"))
    )
    (net (code "75") (name "unconnected-(J1-27-PadPOE1)") (class "Default")
      (node (ref "J1") (pin "POE1") (pinfunction "27_POE1") (pintype "bidirectional"))
    )
    (net (code "76") (name "unconnected-(J3-Pad6)") (class "Default")
      (node (ref "J3") (pin "6") (pinfunction "6_6") (pintype "passive"))
    )
  )
)
